# bq24616_battery_charger.net
KiCad netlist of a schematic drawn in EAGLE
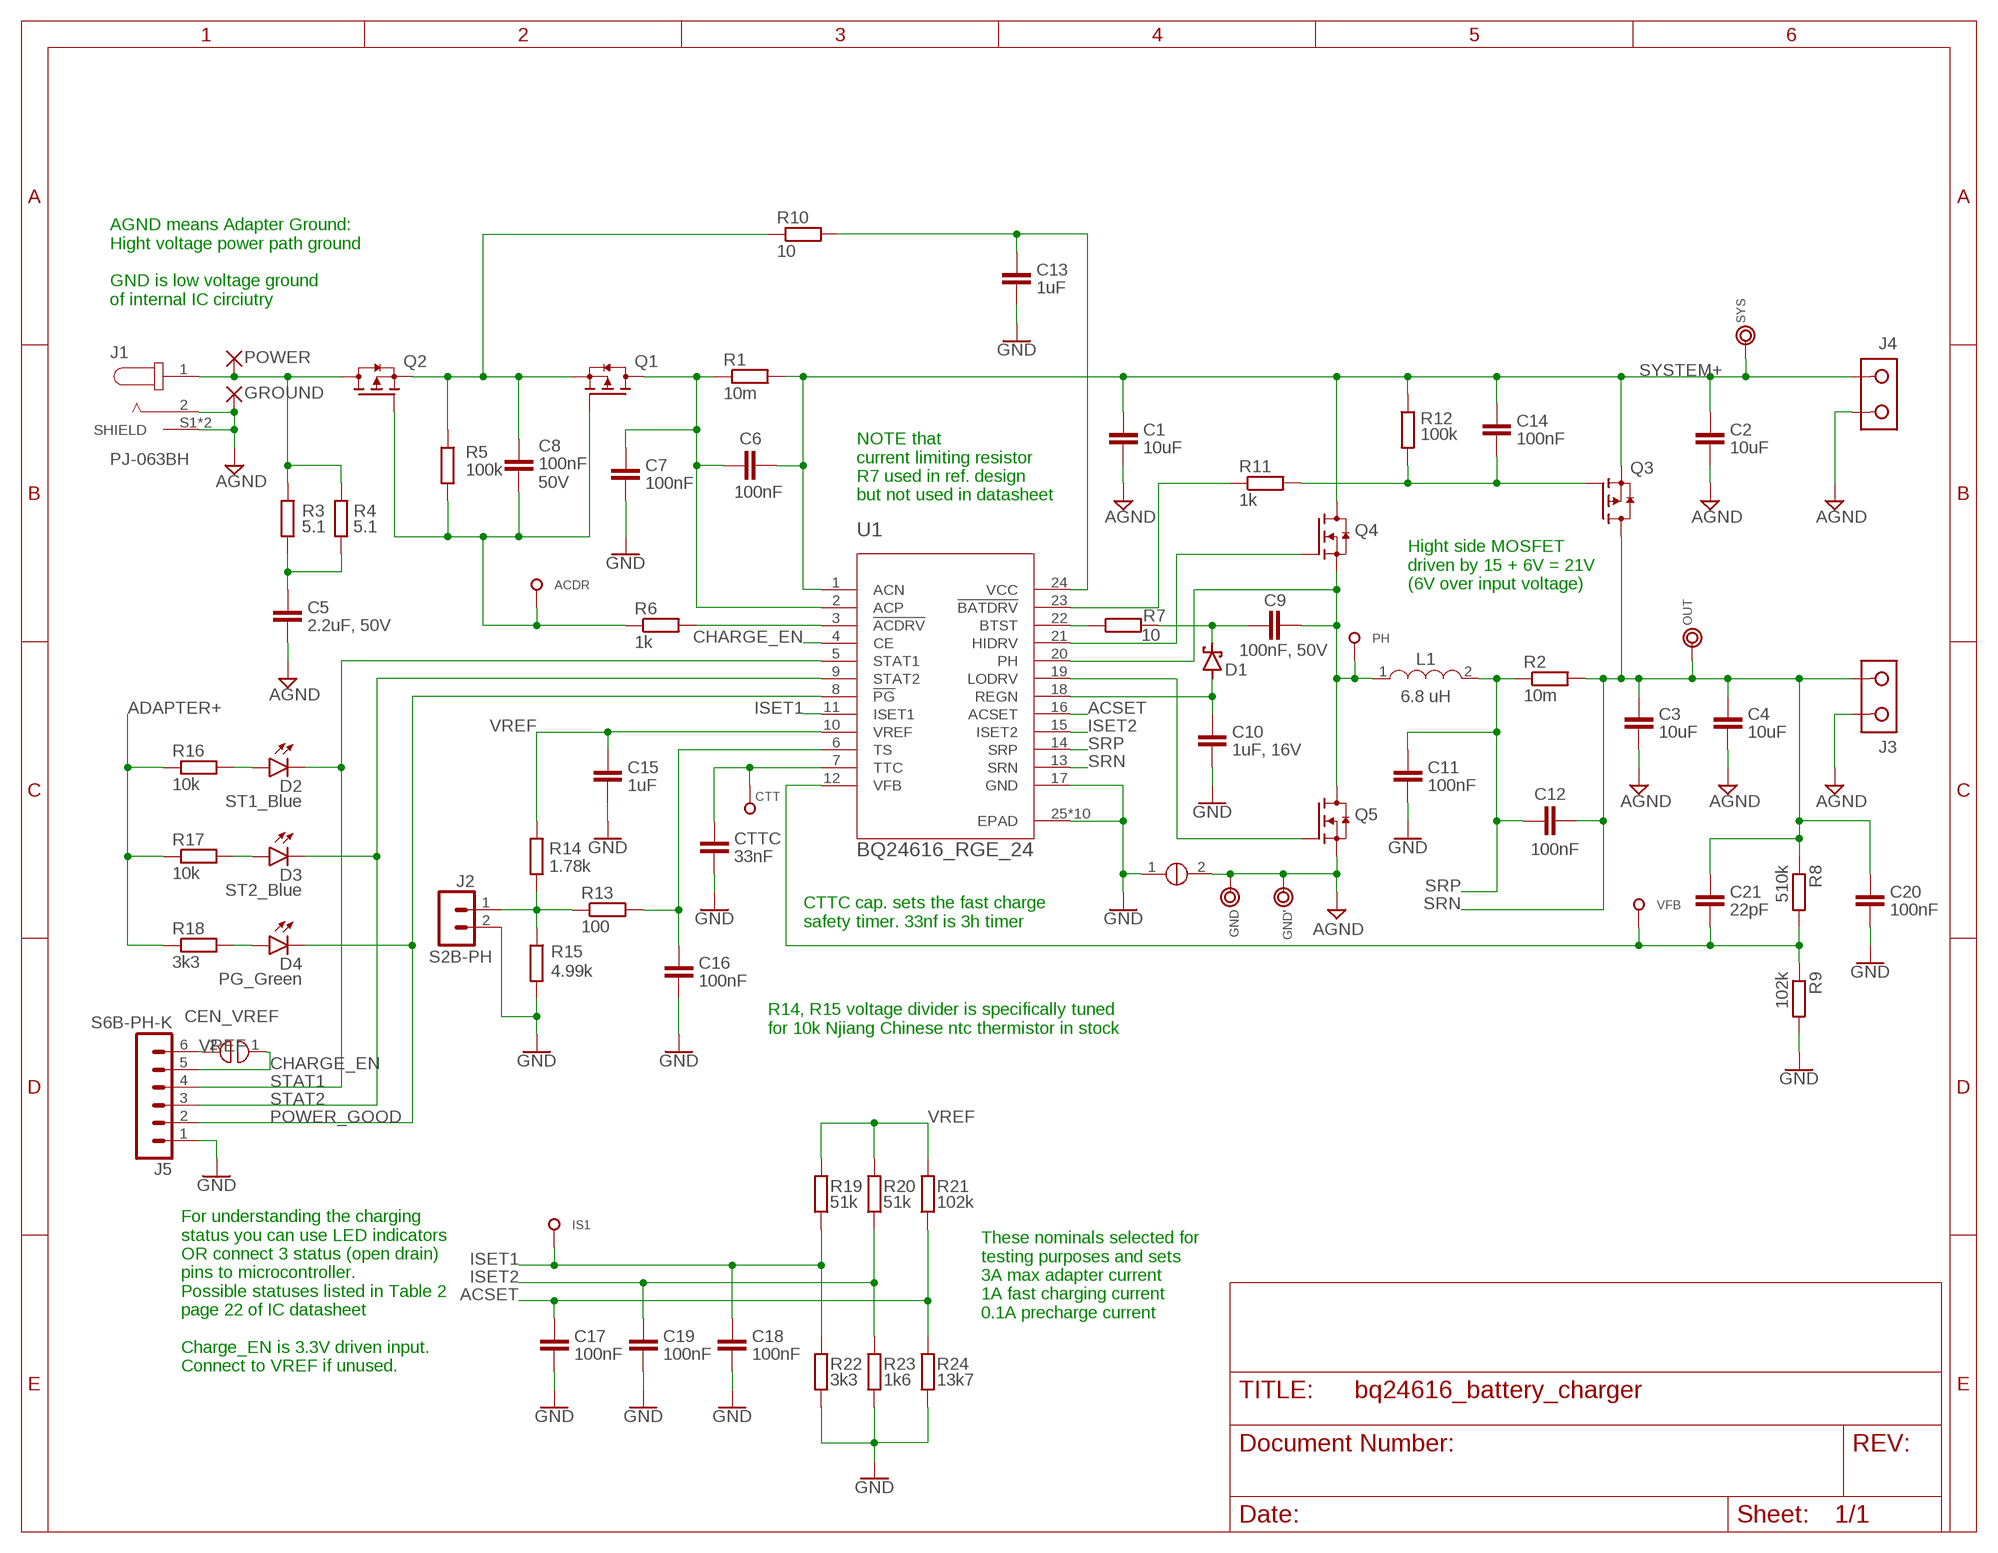
[diagram p0: schematic, sheet 1]

(export (version "E")
  (design (tool "Eeschema 10.0.6"))
  (components
    (comp (ref "ACDR")
      (value "TEST_PAD-[1.27MM]")
      (footprint "eagle-import:TP1.27MM")
      (libsource (lib "eagle-import") (part "TEST_PAD-[1.27MM]"))
    )
    (comp (ref "C1")
      (value "10uF")
      (footprint "eagle-import:C1206")
      (libsource (lib "eagle-import") (part "C-EU-CERAMIC1206"))
    )
    (comp (ref "C2")
      (value "10uF")
      (footprint "eagle-import:C1206")
      (libsource (lib "eagle-import") (part "C-EU-CERAMIC1206"))
    )
    (comp (ref "C3")
      (value "10uF")
      (footprint "eagle-import:C1206")
      (libsource (lib "eagle-import") (part "C-EU-CERAMIC1206"))
    )
    (comp (ref "C4")
      (value "10uF")
      (footprint "eagle-import:C1206")
      (libsource (lib "eagle-import") (part "C-EU-CERAMIC1206"))
    )
    (comp (ref "C5")
      (value "2.2uF, 50V")
      (footprint "eagle-import:C0805")
      (libsource (lib "eagle-import") (part "C-EU-CERAMIC0805"))
    )
    (comp (ref "C6")
      (value "100nF")
      (footprint "eagle-import:C0603")
      (libsource (lib "eagle-import") (part "C-EU-CERAMIC0603"))
    )
    (comp (ref "C7")
      (value "100nF")
      (footprint "eagle-import:C0603")
      (libsource (lib "eagle-import") (part "C-EU-CERAMIC0603"))
    )
    (comp (ref "C8")
      (value "100nF")
      (footprint "eagle-import:C0603")
      (libsource (lib "eagle-import") (part "C-EU-CERAMIC0603"))
    )
    (comp (ref "C9")
      (value "100nF, 50V")
      (footprint "eagle-import:C0603")
      (libsource (lib "eagle-import") (part "C-EU-CERAMIC0603"))
    )
    (comp (ref "C10")
      (value "1uF, 16V")
      (footprint "eagle-import:C0603")
      (libsource (lib "eagle-import") (part "C-EU-CERAMIC0603"))
    )
    (comp (ref "C11")
      (value "100nF")
      (footprint "eagle-import:C0603")
      (libsource (lib "eagle-import") (part "C-EU-CERAMIC0603"))
    )
    (comp (ref "C12")
      (value "100nF")
      (footprint "eagle-import:C0603")
      (libsource (lib "eagle-import") (part "C-EU-CERAMIC0603"))
    )
    (comp (ref "C13")
      (value "1uF")
      (footprint "eagle-import:C0603")
      (libsource (lib "eagle-import") (part "C-EU-CERAMIC0603"))
    )
    (comp (ref "C14")
      (value "100nF")
      (footprint "eagle-import:C0603")
      (libsource (lib "eagle-import") (part "C-EU-CERAMIC0603"))
    )
    (comp (ref "C15")
      (value "1uF")
      (footprint "eagle-import:C0603")
      (libsource (lib "eagle-import") (part "C-EU-CERAMIC0603"))
    )
    (comp (ref "C16")
      (value "100nF")
      (footprint "eagle-import:C0603")
      (libsource (lib "eagle-import") (part "C-EU-CERAMIC0603"))
    )
    (comp (ref "C17")
      (value "100nF")
      (footprint "eagle-import:C0603")
      (libsource (lib "eagle-import") (part "C-EU-CERAMIC0603"))
    )
    (comp (ref "C18")
      (value "100nF")
      (footprint "eagle-import:C0603")
      (libsource (lib "eagle-import") (part "C-EU-CERAMIC0603"))
    )
    (comp (ref "C19")
      (value "100nF")
      (footprint "eagle-import:C0603")
      (libsource (lib "eagle-import") (part "C-EU-CERAMIC0603"))
    )
    (comp (ref "C20")
      (value "100nF")
      (footprint "eagle-import:C0603")
      (libsource (lib "eagle-import") (part "C-EU-CERAMIC0603"))
    )
    (comp (ref "C21")
      (value "22pF")
      (footprint "eagle-import:C0603")
      (libsource (lib "eagle-import") (part "C-EU-CERAMIC0603"))
    )
    (comp (ref "CEN_VREF")
      (value "SOLDER_BRIDGE")
      (footprint "eagle-import:SOLDER_BRIDGE")
      (libsource (lib "eagle-import") (part "SOLDER_BRIDGE"))
    )
    (comp (ref "CTT")
      (value "TEST_PAD-[1.27MM]")
      (footprint "eagle-import:TP1.27MM")
      (libsource (lib "eagle-import") (part "TEST_PAD-[1.27MM]"))
    )
    (comp (ref "CTTC")
      (value "33nF")
      (footprint "eagle-import:C0603")
      (libsource (lib "eagle-import") (part "C-EU-CERAMIC0603"))
    )
    (comp (ref "D1")
      (value "SOD523-SCHOTTKY")
      (footprint "eagle-import:SOD523")
      (libsource (lib "eagle-import") (part "SOD523-SCHOTTKY"))
    )
    (comp (ref "D2")
      (value "ST1_Blue")
      (footprint "eagle-import:LED-0805")
      (libsource (lib "eagle-import") (part "LED0805"))
    )
    (comp (ref "D3")
      (value "ST2_Blue")
      (footprint "eagle-import:LED-0805")
      (libsource (lib "eagle-import") (part "LED0805"))
    )
    (comp (ref "D4")
      (value "PG_Green")
      (footprint "eagle-import:LED-0805")
      (libsource (lib "eagle-import") (part "LED0805"))
    )
    (comp (ref "GND")
      (value "TEST_RING")
      (footprint "eagle-import:TEST_RING")
      (libsource (lib "eagle-import") (part "TEST_RING"))
    )
    (comp (ref "GND'")
      (value "TEST_RING")
      (footprint "eagle-import:TEST_RING")
      (libsource (lib "eagle-import") (part "TEST_RING"))
    )
    (comp (ref "GROUND")
      (value "WIRE_TO_BOARD_2,54/1,1")
      (footprint "eagle-import:2,54_1,1")
      (libsource (lib "eagle-import") (part "WIRE_TO_BOARD_2,54/1,1"))
    )
    (comp (ref "IS1")
      (value "TEST_PAD-[1.27MM]")
      (footprint "eagle-import:TP1.27MM")
      (libsource (lib "eagle-import") (part "TEST_PAD-[1.27MM]"))
    )
    (comp (ref "J1")
      (value "PJ-063BH")
      (footprint "eagle-import:CUI_PJ-063BH")
      (fields (field (name "MANUFACTURER") "CUI INC"))
      (libsource (lib "eagle-import") (part "PJ-063BH"))
    )
    (comp (ref "J2")
      (value "S2B-PH")
      (footprint "eagle-import:S2B-PH-K")
      (libsource (lib "eagle-import") (part "S2B-PH-K"))
    )
    (comp (ref "J3")
      (value "DG301-2P\"")
      (footprint "eagle-import:DG301-2P")
      (libsource (lib "eagle-import") (part "DG301-2P{dblquote}"))
    )
    (comp (ref "J4")
      (value "DG301-2P\"")
      (footprint "eagle-import:DG301-2P")
      (libsource (lib "eagle-import") (part "DG301-2P{dblquote}"))
    )
    (comp (ref "J5")
      (value "S6B-PH-K")
      (footprint "eagle-import:S6B-PH-K")
      (libsource (lib "eagle-import") (part "S6B-PH-K"))
    )
    (comp (ref "L1")
      (value "6.8 uH")
      (footprint "eagle-import:SMD-0630")
      (libsource (lib "eagle-import") (part "MCS0630-100MN1"))
    )
    (comp (ref "OUT")
      (value "TEST_RING")
      (footprint "eagle-import:TEST_RING")
      (libsource (lib "eagle-import") (part "TEST_RING"))
    )
    (comp (ref "PH")
      (value "TEST_PAD-[1.27MM]")
      (footprint "eagle-import:TP1.27MM")
      (libsource (lib "eagle-import") (part "TEST_PAD-[1.27MM]"))
    )
    (comp (ref "POWER")
      (value "WIRE_TO_BOARD_2,54/1,1")
      (footprint "eagle-import:2,54_1,1")
      (libsource (lib "eagle-import") (part "WIRE_TO_BOARD_2,54/1,1"))
    )
    (comp (ref "Q1")
      (value "SI7121DN-T1-GE3")
      (footprint "eagle-import:VISHAY_SI7121DN-T1-GE3")
      (fields (field (name "LCSC_PART_NUMBER") "C190356") (field (name "MF") "Vishay Siliconix"))
      (libsource (lib "eagle-import") (part "SI7121DN-T1-GE3"))
    )
    (comp (ref "Q2")
      (value "SI7121DN-T1-GE3")
      (footprint "eagle-import:VISHAY_SI7121DN-T1-GE3")
      (fields (field (name "LCSC_PART_NUMBER") "C190356") (field (name "MF") "Vishay Siliconix"))
      (libsource (lib "eagle-import") (part "SI7121DN-T1-GE3"))
    )
    (comp (ref "Q3")
      (value "SI7121DN-T1-GE3")
      (footprint "eagle-import:VISHAY_SI7121DN-T1-GE3")
      (fields (field (name "LCSC_PART_NUMBER") "C190356") (field (name "MF") "Vishay Siliconix"))
      (libsource (lib "eagle-import") (part "SI7121DN-T1-GE3"))
    )
    (comp (ref "Q4")
      (value "SON5X6_MOSFET")
      (footprint "eagle-import:SON5X6")
      (fields (field (name "MANUFACTURER_PART_NUMBER") "CSD18534Q5A"))
      (libsource (lib "eagle-import") (part "SON5X6_MOSFET"))
    )
    (comp (ref "Q5")
      (value "SON5X6_MOSFET")
      (footprint "eagle-import:SON5X6")
      (fields (field (name "MANUFACTURER_PART_NUMBER") "CSD18534Q5A"))
      (libsource (lib "eagle-import") (part "SON5X6_MOSFET"))
    )
    (comp (ref "R1")
      (value "10m")
      (footprint "eagle-import:CS_R0805")
      (libsource (lib "eagle-import") (part "R_EU_CS"))
    )
    (comp (ref "R2")
      (value "10m")
      (footprint "eagle-import:CS_R0805")
      (libsource (lib "eagle-import") (part "R_EU_CS"))
    )
    (comp (ref "R3")
      (value "5.1")
      (footprint "eagle-import:R1206")
      (libsource (lib "eagle-import") (part "R-EU1206"))
    )
    (comp (ref "R4")
      (value "5.1")
      (footprint "eagle-import:R1206")
      (libsource (lib "eagle-import") (part "R-EU1206"))
    )
    (comp (ref "R5")
      (value "100k")
      (footprint "eagle-import:R0603")
      (libsource (lib "eagle-import") (part "R-EU0603"))
    )
    (comp (ref "R6")
      (value "1k")
      (footprint "eagle-import:R0603")
      (libsource (lib "eagle-import") (part "R-EU0603"))
    )
    (comp (ref "R7")
      (value "10")
      (footprint "eagle-import:R0603")
      (libsource (lib "eagle-import") (part "R-EU0603"))
    )
    (comp (ref "R8")
      (value "510k")
      (footprint "eagle-import:R0603")
      (libsource (lib "eagle-import") (part "R-EU0603"))
    )
    (comp (ref "R9")
      (value "102k")
      (footprint "eagle-import:R0603")
      (libsource (lib "eagle-import") (part "R-EU0603"))
    )
    (comp (ref "R10")
      (value "10")
      (footprint "eagle-import:R1206")
      (libsource (lib "eagle-import") (part "R-EU1206"))
    )
    (comp (ref "R11")
      (value "1k")
      (footprint "eagle-import:R0603")
      (libsource (lib "eagle-import") (part "R-EU0603"))
    )
    (comp (ref "R12")
      (value "100k")
      (footprint "eagle-import:R0603")
      (libsource (lib "eagle-import") (part "R-EU0603"))
    )
    (comp (ref "R13")
      (value "100")
      (footprint "eagle-import:R0603")
      (libsource (lib "eagle-import") (part "R-EU0603"))
    )
    (comp (ref "R14")
      (value "1.78k")
      (footprint "eagle-import:R0603")
      (libsource (lib "eagle-import") (part "R-EU0603"))
    )
    (comp (ref "R15")
      (value "4.99k")
      (footprint "eagle-import:R0603")
      (libsource (lib "eagle-import") (part "R-EU0603"))
    )
    (comp (ref "R16")
      (value "10k")
      (footprint "eagle-import:R0603")
      (libsource (lib "eagle-import") (part "R-EU0603"))
    )
    (comp (ref "R17")
      (value "10k")
      (footprint "eagle-import:R0603")
      (libsource (lib "eagle-import") (part "R-EU0603"))
    )
    (comp (ref "R18")
      (value "3k3")
      (footprint "eagle-import:R0603")
      (libsource (lib "eagle-import") (part "R-EU0603"))
    )
    (comp (ref "R19")
      (value "51k")
      (footprint "eagle-import:R0603")
      (libsource (lib "eagle-import") (part "R-EU0603"))
    )
    (comp (ref "R20")
      (value "51k")
      (footprint "eagle-import:R0603")
      (libsource (lib "eagle-import") (part "R-EU0603"))
    )
    (comp (ref "R21")
      (value "102k")
      (footprint "eagle-import:R0603")
      (libsource (lib "eagle-import") (part "R-EU0603"))
    )
    (comp (ref "R22")
      (value "3k3")
      (footprint "eagle-import:R0603")
      (libsource (lib "eagle-import") (part "R-EU0603"))
    )
    (comp (ref "R23")
      (value "1k6")
      (footprint "eagle-import:R0603")
      (libsource (lib "eagle-import") (part "R-EU0603"))
    )
    (comp (ref "R24")
      (value "13k7")
      (footprint "eagle-import:R0603")
      (libsource (lib "eagle-import") (part "R-EU0603"))
    )
    (comp (ref "SB2")
      (value "SHORT")
      (footprint "eagle-import:SHORT")
      (libsource (lib "eagle-import") (part "SHORT"))
    )
    (comp (ref "SYS")
      (value "TEST_RING")
      (footprint "eagle-import:TEST_RING")
      (libsource (lib "eagle-import") (part "TEST_RING"))
    )
    (comp (ref "U1")
      (value "BQ24616_RGE_24")
      (footprint "eagle-import:RGE24_2P45X2P45")
      (fields
        (field (name "GENERIC_PART_NUMBER") "BQ24616")
        (field (name "MANUFACTURER") "Texas Instruments")
      )
      (libsource (lib "eagle-import") (part "BQ24616_RGE_24"))
    )
    (comp (ref "VFB")
      (value "TEST_PAD-[1.27MM]")
      (footprint "eagle-import:TP1.27MM")
      (libsource (lib "eagle-import") (part "TEST_PAD-[1.27MM]"))
    )
  )
  (nets
    (net (code "1") (name "/ACSET") (class "Default")
      (node (ref "C17") (pin "1") (pinfunction "1_1") (pintype "passive"))
      (node (ref "R21") (pin "1") (pinfunction "1_1") (pintype "passive"))
      (node (ref "R24") (pin "2") (pinfunction "2_2") (pintype "passive"))
      (node (ref "U1") (pin "16") (pinfunction "ACSET_16") (pintype "input"))
    )
    (net (code "2") (name "/ADAPTER+") (class "Default")
      (node (ref "J1") (pin "1") (pinfunction "1_1") (pintype "passive"))
      (node (ref "POWER") (pin "1") (pinfunction "P_1") (pintype "passive"))
      (node (ref "Q2") (pin "5") (pinfunction "D_5") (pintype "passive"))
      (node (ref "Q2") (pin "6") (pinfunction "D_6") (pintype "passive"))
      (node (ref "Q2") (pin "7") (pinfunction "D_7") (pintype "passive"))
      (node (ref "Q2") (pin "8") (pinfunction "D_8") (pintype "passive"))
      (node (ref "Q2") (pin "9") (pinfunction "D_9") (pintype "passive"))
      (node (ref "R16") (pin "1") (pinfunction "1_1") (pintype "passive"))
      (node (ref "R17") (pin "1") (pinfunction "1_1") (pintype "passive"))
      (node (ref "R18") (pin "1") (pinfunction "1_1") (pintype "passive"))
      (node (ref "R3") (pin "2") (pinfunction "2_2") (pintype "passive"))
      (node (ref "R4") (pin "2") (pinfunction "2_2") (pintype "passive"))
    )
    (net (code "3") (name "/CHARGE_EN") (class "Default")
      (node (ref "CEN_VREF") (pin "1") (pinfunction "1_1") (pintype "passive"))
      (node (ref "J5") (pin "5") (pinfunction "5_5") (pintype "passive"))
      (node (ref "U1") (pin "4") (pinfunction "CE_4") (pintype "input"))
    )
    (net (code "4") (name "/ISET1") (class "Default")
      (node (ref "C18") (pin "1") (pinfunction "1_1") (pintype "passive"))
      (node (ref "IS1") (pin "1") (pinfunction "P$1_1") (pintype "bidirectional"))
      (node (ref "R19") (pin "1") (pinfunction "1_1") (pintype "passive"))
      (node (ref "R22") (pin "2") (pinfunction "2_2") (pintype "passive"))
      (node (ref "U1") (pin "11") (pinfunction "ISET1_11") (pintype "input"))
    )
    (net (code "5") (name "/ISET2") (class "Default")
      (node (ref "C19") (pin "1") (pinfunction "1_1") (pintype "passive"))
      (node (ref "R20") (pin "1") (pinfunction "1_1") (pintype "passive"))
      (node (ref "R23") (pin "2") (pinfunction "2_2") (pintype "passive"))
      (node (ref "U1") (pin "15") (pinfunction "ISET2_15") (pintype "input"))
    )
    (net (code "6") (name "/POWER_GOOD") (class "Default")
      (node (ref "D4") (pin "-") (pinfunction "C_-") (pintype "passive"))
      (node (ref "J5") (pin "2") (pinfunction "2_2") (pintype "passive"))
      (node (ref "U1") (pin "8") (pinfunction "~{PG}_8") (pintype "input"))
    )
    (net (code "7") (name "/SRN") (class "Default")
      (node (ref "C12") (pin "2") (pinfunction "2_2") (pintype "passive"))
      (node (ref "C20") (pin "1") (pinfunction "1_1") (pintype "passive"))
      (node (ref "C21") (pin "1") (pinfunction "1_1") (pintype "passive"))
      (node (ref "C3") (pin "1") (pinfunction "1_1") (pintype "passive"))
      (node (ref "C4") (pin "1") (pinfunction "1_1") (pintype "passive"))
      (node (ref "J3") (pin "2") (pinfunction "2_2") (pintype "passive"))
      (node (ref "OUT") (pin "1") (pinfunction "P$1_1") (pintype "bidirectional"))
      (node (ref "Q3") (pin "5") (pinfunction "D_5") (pintype "passive"))
      (node (ref "Q3") (pin "6") (pinfunction "D_6") (pintype "passive"))
      (node (ref "Q3") (pin "7") (pinfunction "D_7") (pintype "passive"))
      (node (ref "Q3") (pin "8") (pinfunction "D_8") (pintype "passive"))
      (node (ref "Q3") (pin "9") (pinfunction "D_9") (pintype "passive"))
      (node (ref "R2") (pin "2") (pinfunction "2_2") (pintype "passive"))
      (node (ref "R8") (pin "1") (pinfunction "1_1") (pintype "passive"))
      (node (ref "U1") (pin "13") (pinfunction "SRN_13") (pintype "output"))
    )
    (net (code "8") (name "/SRP") (class "Default")
      (node (ref "C11") (pin "1") (pinfunction "1_1") (pintype "passive"))
      (node (ref "C12") (pin "1") (pinfunction "1_1") (pintype "passive"))
      (node (ref "L1") (pin "2") (pinfunction "2_2") (pintype "bidirectional"))
      (node (ref "R2") (pin "1") (pinfunction "1_1") (pintype "passive"))
      (node (ref "U1") (pin "14") (pinfunction "SRP_14") (pintype "output"))
    )
    (net (code "9") (name "/STAT1") (class "Default")
      (node (ref "D2") (pin "-") (pinfunction "C_-") (pintype "passive"))
      (node (ref "J5") (pin "4") (pinfunction "4_4") (pintype "passive"))
      (node (ref "U1") (pin "5") (pinfunction "STAT1_5") (pintype "input"))
    )
    (net (code "10") (name "/STAT2") (class "Default")
      (node (ref "D3") (pin "-") (pinfunction "C_-") (pintype "passive"))
      (node (ref "J5") (pin "3") (pinfunction "3_3") (pintype "passive"))
      (node (ref "U1") (pin "9") (pinfunction "STAT2_9") (pintype "input"))
    )
    (net (code "11") (name "/SYSTEM+") (class "Default")
      (node (ref "C1") (pin "1") (pinfunction "1_1") (pintype "passive"))
      (node (ref "C14") (pin "1") (pinfunction "1_1") (pintype "passive"))
      (node (ref "C2") (pin "1") (pinfunction "1_1") (pintype "passive"))
      (node (ref "C6") (pin "2") (pinfunction "2_2") (pintype "passive"))
      (node (ref "J4") (pin "1") (pinfunction "1_1") (pintype "passive"))
      (node (ref "Q3") (pin "1") (pinfunction "S_1") (pintype "passive"))
      (node (ref "Q3") (pin "2") (pinfunction "S_2") (pintype "passive"))
      (node (ref "Q3") (pin "3") (pinfunction "S_3") (pintype "passive"))
      (node (ref "Q4") (pin "5") (pinfunction "D_5") (pintype "passive"))
      (node (ref "Q4") (pin "6") (pinfunction "D_6") (pintype "passive"))
      (node (ref "Q4") (pin "7") (pinfunction "D_7") (pintype "passive"))
      (node (ref "Q4") (pin "8") (pinfunction "D_8") (pintype "passive"))
      (node (ref "Q4") (pin "9") (pinfunction "D_9") (pintype "passive"))
      (node (ref "R1") (pin "2") (pinfunction "2_2") (pintype "passive"))
      (node (ref "R12") (pin "1") (pinfunction "1_1") (pintype "passive"))
      (node (ref "SYS") (pin "1") (pinfunction "P$1_1") (pintype "bidirectional"))
      (node (ref "U1") (pin "1") (pinfunction "ACN_1") (pintype "input"))
    )
    (net (code "12") (name "/VREF") (class "Default")
      (node (ref "C15") (pin "1") (pinfunction "1_1") (pintype "passive"))
      (node (ref "CEN_VREF") (pin "2") (pinfunction "2_2") (pintype "passive"))
      (node (ref "J5") (pin "6") (pinfunction "6_6") (pintype "passive"))
      (node (ref "R14") (pin "1") (pinfunction "1_1") (pintype "passive"))
      (node (ref "R19") (pin "2") (pinfunction "2_2") (pintype "passive"))
      (node (ref "R20") (pin "2") (pinfunction "2_2") (pintype "passive"))
      (node (ref "R21") (pin "2") (pinfunction "2_2") (pintype "passive"))
      (node (ref "U1") (pin "10") (pinfunction "VREF_10") (pintype "input"))
    )
    (net (code "13") (name "AGND") (class "Default")
      (node (ref "C1") (pin "2") (pinfunction "2_2") (pintype "passive"))
      (node (ref "C2") (pin "2") (pinfunction "2_2") (pintype "passive"))
      (node (ref "C3") (pin "2") (pinfunction "2_2") (pintype "passive"))
      (node (ref "C4") (pin "2") (pinfunction "2_2") (pintype "passive"))
      (node (ref "C5") (pin "2") (pinfunction "2_2") (pintype "passive"))
      (node (ref "GND") (pin "1") (pinfunction "P$1_1") (pintype "bidirectional"))
      (node (ref "GND'") (pin "1") (pinfunction "P$1_1") (pintype "bidirectional"))
      (node (ref "GROUND") (pin "1") (pinfunction "P_1") (pintype "passive"))
      (node (ref "J1") (pin "2") (pinfunction "2_2") (pintype "passive"))
      (node (ref "J1") (pin "S1") (pinfunction "SHIELD_S1") (pintype "power_in"))
      (node (ref "J1") (pin "S2") (pinfunction "SHIELD_S2") (pintype "power_in"))
      (node (ref "J3") (pin "1") (pinfunction "1_1") (pintype "passive"))
      (node (ref "J4") (pin "2") (pinfunction "2_2") (pintype "passive"))
      (node (ref "Q5") (pin "1") (pinfunction "S_1") (pintype "passive"))
      (node (ref "Q5") (pin "2") (pinfunction "S_2") (pintype "passive"))
      (node (ref "Q5") (pin "3") (pinfunction "S_3") (pintype "passive"))
      (node (ref "SB2") (pin "2") (pinfunction "2_2") (pintype "passive"))
    )
    (net (code "14") (name "GND") (class "Default")
      (node (ref "C10") (pin "2") (pinfunction "2_2") (pintype "passive"))
      (node (ref "C11") (pin "2") (pinfunction "2_2") (pintype "passive"))
      (node (ref "C13") (pin "2") (pinfunction "2_2") (pintype "passive"))
      (node (ref "C15") (pin "2") (pinfunction "2_2") (pintype "passive"))
      (node (ref "C16") (pin "2") (pinfunction "2_2") (pintype "passive"))
      (node (ref "C17") (pin "2") (pinfunction "2_2") (pintype "passive"))
      (node (ref "C18") (pin "2") (pinfunction "2_2") (pintype "passive"))
      (node (ref "C19") (pin "2") (pinfunction "2_2") (pintype "passive"))
      (node (ref "C20") (pin "2") (pinfunction "2_2") (pintype "passive"))
      (node (ref "C7") (pin "2") (pinfunction "2_2") (pintype "passive"))
      (node (ref "CTTC") (pin "2") (pinfunction "2_2") (pintype "passive"))
      (node (ref "J2") (pin "2") (pinfunction "2_2") (pintype "passive"))
      (node (ref "J5") (pin "1") (pinfunction "1_1") (pintype "passive"))
      (node (ref "R15") (pin "2") (pinfunction "2_2") (pintype "passive"))
      (node (ref "R22") (pin "1") (pinfunction "1_1") (pintype "passive"))
      (node (ref "R23") (pin "1") (pinfunction "1_1") (pintype "passive"))
      (node (ref "R24") (pin "1") (pinfunction "1_1") (pintype "passive"))
      (node (ref "R9") (pin "2") (pinfunction "2_2") (pintype "passive"))
      (node (ref "SB2") (pin "1") (pinfunction "1_1") (pintype "passive"))
      (node (ref "U1") (pin "17") (pinfunction "GND_17") (pintype "power_in"))
      (node (ref "U1") (pin "25") (pinfunction "EPAD_25") (pintype "power_in"))
      (node (ref "U1") (pin "V") (pinfunction "EPAD_V") (pintype "power_in"))
      (node (ref "U1") (pin "V_1") (pinfunction "EPAD_V_1") (pintype "power_in"))
      (node (ref "U1") (pin "V_2") (pinfunction "EPAD_V_2") (pintype "power_in"))
      (node (ref "U1") (pin "V_3") (pinfunction "EPAD_V_3") (pintype "power_in"))
      (node (ref "U1") (pin "V_4") (pinfunction "EPAD_V_4") (pintype "power_in"))
      (node (ref "U1") (pin "V_5") (pinfunction "EPAD_V_5") (pintype "power_in"))
      (node (ref "U1") (pin "V_6") (pinfunction "EPAD_V_6") (pintype "power_in"))
      (node (ref "U1") (pin "V_7") (pinfunction "EPAD_V_7") (pintype "power_in"))
      (node (ref "U1") (pin "V_8") (pinfunction "EPAD_V_8") (pintype "power_in"))
    )
    (net (code "15") (name "Net-(ACDR-P$1)") (class "Default")
      (node (ref "ACDR") (pin "1") (pinfunction "P$1_1") (pintype "bidirectional"))
      (node (ref "C8") (pin "2") (pinfunction "2_2") (pintype "passive"))
      (node (ref "Q1") (pin "4") (pinfunction "G_4") (pintype "passive"))
      (node (ref "Q2") (pin "4") (pinfunction "G_4") (pintype "passive"))
      (node (ref "R5") (pin "2") (pinfunction "2_2") (pintype "passive"))
      (node (ref "R6") (pin "1") (pinfunction "1_1") (pintype "passive"))
    )
    (net (code "16") (name "Net-(C5-Pad1)") (class "Default")
      (node (ref "C5") (pin "1") (pinfunction "1_1") (pintype "passive"))
      (node (ref "R3") (pin "1") (pinfunction "1_1") (pintype "passive"))
      (node (ref "R4") (pin "1") (pinfunction "1_1") (pintype "passive"))
    )
    (net (code "17") (name "Net-(C8-Pad1)") (class "Default")
      (node (ref "C8") (pin "1") (pinfunction "1_1") (pintype "passive"))
      (node (ref "Q1") (pin "1") (pinfunction "S_1") (pintype "passive"))
      (node (ref "Q1") (pin "2") (pinfunction "S_2") (pintype "passive"))
      (node (ref "Q1") (pin "3") (pinfunction "S_3") (pintype "passive"))
      (node (ref "Q2") (pin "1") (pinfunction "S_1") (pintype "passive"))
      (node (ref "Q2") (pin "2") (pinfunction "S_2") (pintype "passive"))
      (node (ref "Q2") (pin "3") (pinfunction "S_3") (pintype "passive"))
      (node (ref "R10") (pin "1") (pinfunction "1_1") (pintype "passive"))
      (node (ref "R5") (pin "1") (pinfunction "1_1") (pintype "passive"))
    )
    (net (code "18") (name "Net-(C9-Pad1)") (class "Default")
      (node (ref "C9") (pin "1") (pinfunction "1_1") (pintype "passive"))
      (node (ref "D1") (pin "C") (pinfunction "C_C") (pintype "passive"))
      (node (ref "R7") (pin "2") (pinfunction "2_2") (pintype "passive"))
    )
    (net (code "19") (name "Net-(CTT-P$1)") (class "Default")
      (node (ref "CTT") (pin "1") (pinfunction "P$1_1") (pintype "bidirectional"))
      (node (ref "CTTC") (pin "1") (pinfunction "1_1") (pintype "passive"))
      (node (ref "U1") (pin "7") (pinfunction "TTC_7") (pintype "output"))
    )
    (net (code "20") (name "Net-(D2-A)") (class "Default")
      (node (ref "D2") (pin "+") (pinfunction "A_+") (pintype "passive"))
      (node (ref "R16") (pin "2") (pinfunction "2_2") (pintype "passive"))
    )
    (net (code "21") (name "Net-(D3-A)") (class "Default")
      (node (ref "D3") (pin "+") (pinfunction "A_+") (pintype "passive"))
      (node (ref "R17") (pin "2") (pinfunction "2_2") (pintype "passive"))
    )
    (net (code "22") (name "Net-(D4-A)") (class "Default")
      (node (ref "D4") (pin "+") (pinfunction "A_+") (pintype "passive"))
      (node (ref "R18") (pin "2") (pinfunction "2_2") (pintype "passive"))
    )
    (net (code "23") (name "Net-(J2-Pad1)") (class "Default")
      (node (ref "J2") (pin "1") (pinfunction "1_1") (pintype "passive"))
      (node (ref "R13") (pin "1") (pinfunction "1_1") (pintype "passive"))
      (node (ref "R14") (pin "2") (pinfunction "2_2") (pintype "passive"))
      (node (ref "R15") (pin "1") (pinfunction "1_1") (pintype "passive"))
    )
    (net (code "24") (name "Net-(PH-P$1)") (class "Default")
      (node (ref "C9") (pin "2") (pinfunction "2_2") (pintype "passive"))
      (node (ref "L1") (pin "1") (pinfunction "1_1") (pintype "bidirectional"))
      (node (ref "PH") (pin "1") (pinfunction "P$1_1") (pintype "bidirectional"))
      (node (ref "Q4") (pin "1") (pinfunction "S_1") (pintype "passive"))
      (node (ref "Q4") (pin "2") (pinfunction "S_2") (pintype "passive"))
      (node (ref "Q4") (pin "3") (pinfunction "S_3") (pintype "passive"))
      (node (ref "Q5") (pin "5") (pinfunction "D_5") (pintype "passive"))
      (node (ref "Q5") (pin "6") (pinfunction "D_6") (pintype "passive"))
      (node (ref "Q5") (pin "7") (pinfunction "D_7") (pintype "passive"))
      (node (ref "Q5") (pin "8") (pinfunction "D_8") (pintype "passive"))
      (node (ref "Q5") (pin "9") (pinfunction "D_9") (pintype "passive"))
      (node (ref "U1") (pin "20") (pinfunction "PH_20") (pintype "output"))
    )
    (net (code "25") (name "Net-(Q3-G)") (class "Default")
      (node (ref "C14") (pin "2") (pinfunction "2_2") (pintype "passive"))
      (node (ref "Q3") (pin "4") (pinfunction "G_4") (pintype "passive"))
      (node (ref "R11") (pin "2") (pinfunction "2_2") (pintype "passive"))
      (node (ref "R12") (pin "2") (pinfunction "2_2") (pintype "passive"))
    )
    (net (code "26") (name "Net-(Q4-G)") (class "Default")
      (node (ref "Q4") (pin "4") (pinfunction "G_4") (pintype "passive"))
      (node (ref "U1") (pin "21") (pinfunction "HIDRV_21") (pintype "output"))
    )
    (net (code "27") (name "Net-(Q5-G)") (class "Default")
      (node (ref "Q5") (pin "4") (pinfunction "G_4") (pintype "passive"))
      (node (ref "U1") (pin "19") (pinfunction "LODRV_19") (pintype "output"))
    )
    (net (code "28") (name "Net-(U1-ACP)") (class "Default")
      (node (ref "C6") (pin "1") (pinfunction "1_1") (pintype "passive"))
      (node (ref "C7") (pin "1") (pinfunction "1_1") (pintype "passive"))
      (node (ref "Q1") (pin "5") (pinfunction "D_5") (pintype "passive"))
      (node (ref "Q1") (pin "6") (pinfunction "D_6") (pintype "passive"))
      (node (ref "Q1") (pin "7") (pinfunction "D_7") (pintype "passive"))
      (node (ref "Q1") (pin "8") (pinfunction "D_8") (pintype "passive"))
      (node (ref "Q1") (pin "9") (pinfunction "D_9") (pintype "passive"))
      (node (ref "R1") (pin "1") (pinfunction "1_1") (pintype "passive"))
      (node (ref "U1") (pin "2") (pinfunction "ACP_2") (pintype "input"))
    )
    (net (code "29") (name "Net-(U1-BTST)") (class "Default")
      (node (ref "R7") (pin "1") (pinfunction "1_1") (pintype "passive"))
      (node (ref "U1") (pin "22") (pinfunction "BTST_22") (pintype "output"))
    )
    (net (code "30") (name "Net-(U1-REGN)") (class "Default")
      (node (ref "C10") (pin "1") (pinfunction "1_1") (pintype "passive"))
      (node (ref "D1") (pin "A") (pinfunction "A_A") (pintype "passive"))
      (node (ref "U1") (pin "18") (pinfunction "REGN_18") (pintype "output"))
    )
    (net (code "31") (name "Net-(U1-TS)") (class "Default")
      (node (ref "C16") (pin "1") (pinfunction "1_1") (pintype "passive"))
      (node (ref "R13") (pin "2") (pinfunction "2_2") (pintype "passive"))
      (node (ref "U1") (pin "6") (pinfunction "TS_6") (pintype "input"))
    )
    (net (code "32") (name "Net-(U1-VCC)") (class "Default")
      (node (ref "C13") (pin "1") (pinfunction "1_1") (pintype "passive"))
      (node (ref "R10") (pin "2") (pinfunction "2_2") (pintype "passive"))
      (node (ref "U1") (pin "24") (pinfunction "VCC_24") (pintype "power_in"))
    )
    (net (code "33") (name "Net-(U1-VFB)") (class "Default")
      (node (ref "C21") (pin "2") (pinfunction "2_2") (pintype "passive"))
      (node (ref "R8") (pin "2") (pinfunction "2_2") (pintype "passive"))
      (node (ref "R9") (pin "1") (pinfunction "1_1") (pintype "passive"))
      (node (ref "U1") (pin "12") (pinfunction "VFB_12") (pintype "output"))
      (node (ref "VFB") (pin "1") (pinfunction "P$1_1") (pintype "bidirectional"))
    )
    (net (code "34") (name "Net-(U1-~{ACDRV})") (class "Default")
      (node (ref "R6") (pin "2") (pinfunction "2_2") (pintype "passive"))
      (node (ref "U1") (pin "3") (pinfunction "~{ACDRV}_3") (pintype "input"))
    )
    (net (code "35") (name "Net-(U1-~{BATDRV})") (class "Default")
      (node (ref "R11") (pin "1") (pinfunction "1_1") (pintype "passive"))
      (node (ref "U1") (pin "23") (pinfunction "~{BATDRV}_23") (pintype "output"))
    )
  )
)
